# Sheet1.net
KiCad netlist of a schematic drawn in Altium Designer
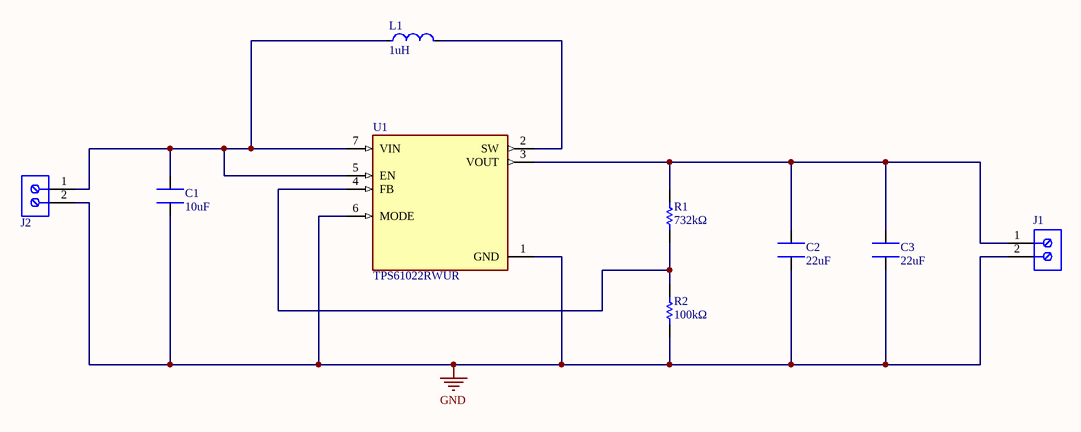
[diagram p0: Sheet1.SchDoc]

(export (version "E")
  (design (tool "Eeschema 10.0.6"))
  (components
    (comp (ref "C1")
      (value "10uF")
      (footprint "CL21A106KPFNNNE")
      (description "10V 10uF X5R ±10% 0805 Multilayer Ceramic Capacitors MLCC - SMD/SMT ROHS")
      (fields (field (name "TOLERANCE") "10%"))
      (libsource (lib "Integrated_Library1") (part "CL21A106KPFNNNE"))
    )
    (comp (ref "C2")
      (value "22uF")
      (footprint "CL21A226KOQNNNE")
      (description "16V 22uF X5R ±10% 0805 Multilayer Ceramic Capacitors MLCC - SMD/SMT ROHS")
      (fields (field (name "TOLERANCE") "10%"))
      (libsource (lib "Integrated_Library1") (part "CL21A226KOQNNNE"))
    )
    (comp (ref "C3")
      (value "22uF")
      (footprint "CL21A226KOQNNNE")
      (description "16V 22uF X5R ±10% 0805 Multilayer Ceramic Capacitors MLCC - SMD/SMT ROHS")
      (fields (field (name "TOLERANCE") "10%"))
      (libsource (lib "Integrated_Library1") (part "CL21A226KOQNNNE"))
    )
    (comp (ref "J1")
      (value "691709710302")
      (footprint "WURTH_691709710302")
      (description "Conn Terminal Block F 2 POS 5mm Solder RA SMD 6A T/R")
      (fields (field (name "VOLTAGE") "300V"))
      (libsource (lib "Integrated_Library1") (part "691709710302"))
    )
    (comp (ref "J2")
      (value "691709710302")
      (footprint "WURTH_691709710302")
      (description "Conn Terminal Block F 2 POS 5mm Solder RA SMD 6A T/R")
      (fields (field (name "VOLTAGE") "300V"))
      (libsource (lib "Integrated_Library1") (part "691709710302"))
    )
    (comp (ref "L1")
      (value "1uH")
      (footprint "SPM10054T-1R0M-HZ")
      (description "27.5A 1uH ±20% 24A 2.4mΩ - Inductors (SMD) ROHS")
      (libsource (lib "Integrated_Library1") (part "SPM10054T-1R0M-HZ"))
    )
    (comp (ref "R1")
      (value "732kΩ")
      (footprint "0805W8F7323T5E")
      (fields
        (field (name "MANUFACTURER") "UNI-ROYAL(Uniroyal Elec)")
        (field (name "MANUFACTURER PART NUMBER") "0805W8F7323T5E")
      )
      (libsource (lib "Integrated_Library1") (part "0805W8F7323T5E"))
    )
    (comp (ref "R2")
      (value "100kΩ")
      (footprint "CRCW0402100KFKED")
      (description "±1% 63mW 75V ±100ppm/K 100kΩ -55℃~+155℃ 0402 Chip Resistor - Surface Mount ROHS")
      (fields (field (name "TOLERANCE") "1%"))
      (libsource (lib "Integrated_Library1") (part "CRCW0402100KFKED"))
    )
    (comp (ref "U1")
      (value "TPS61022RWUR")
      (footprint "TPS61022RWUR")
      (description "8-A boost converter with 0.5-V ultra-low input voltage 7-VQFN-HR -40 to 125")
      (libsource (lib "Integrated_Library1") (part "TPS61022RWUR"))
    )
  )
  (nets
    (net (code "1") (name "GND") (class "Default")
      (node (ref "C1") (pin "1") (pinfunction "1_1") (pintype "passive"))
      (node (ref "C2") (pin "2") (pinfunction "2_2") (pintype "passive"))
      (node (ref "C3") (pin "2") (pinfunction "2_2") (pintype "passive"))
      (node (ref "J1") (pin "2") (pinfunction "2_2") (pintype "passive"))
      (node (ref "J2") (pin "2") (pinfunction "2_2") (pintype "passive"))
      (node (ref "R2") (pin "1") (pinfunction "1_1") (pintype "passive"))
      (node (ref "U1") (pin "1") (pinfunction "GND_1") (pintype "power_in"))
      (node (ref "U1") (pin "6") (pinfunction "MODE_6") (pintype "input"))
    )
    (net (code "2") (name "Net-(U1-EN)") (class "Default")
      (node (ref "C1") (pin "2") (pinfunction "2_2") (pintype "passive"))
      (node (ref "J2") (pin "1") (pinfunction "1_1") (pintype "passive"))
      (node (ref "L1") (pin "1") (pinfunction "1_1") (pintype "passive"))
      (node (ref "U1") (pin "5") (pinfunction "EN_5") (pintype "input"))
      (node (ref "U1") (pin "7") (pinfunction "VIN_7") (pintype "input"))
    )
    (net (code "3") (name "Net-(U1-FB)") (class "Default")
      (node (ref "R1") (pin "1") (pinfunction "1_1") (pintype "passive"))
      (node (ref "R2") (pin "2") (pinfunction "2_2") (pintype "passive"))
      (node (ref "U1") (pin "4") (pinfunction "FB_4") (pintype "input"))
    )
    (net (code "4") (name "Net-(U1-SW)") (class "Default")
      (node (ref "L1") (pin "2") (pinfunction "2_2") (pintype "passive"))
      (node (ref "U1") (pin "2") (pinfunction "SW_2") (pintype "output"))
    )
    (net (code "5") (name "Net-(U1-VOUT)") (class "Default")
      (node (ref "C2") (pin "1") (pinfunction "1_1") (pintype "passive"))
      (node (ref "C3") (pin "1") (pinfunction "1_1") (pintype "passive"))
      (node (ref "J1") (pin "1") (pinfunction "1_1") (pintype "passive"))
      (node (ref "R1") (pin "2") (pinfunction "2_2") (pintype "passive"))
      (node (ref "U1") (pin "3") (pinfunction "VOUT_3") (pintype "output"))
    )
  )
)
